# 2312_ESP32.net
KiCad netlist of a schematic drawn in Altium Designer
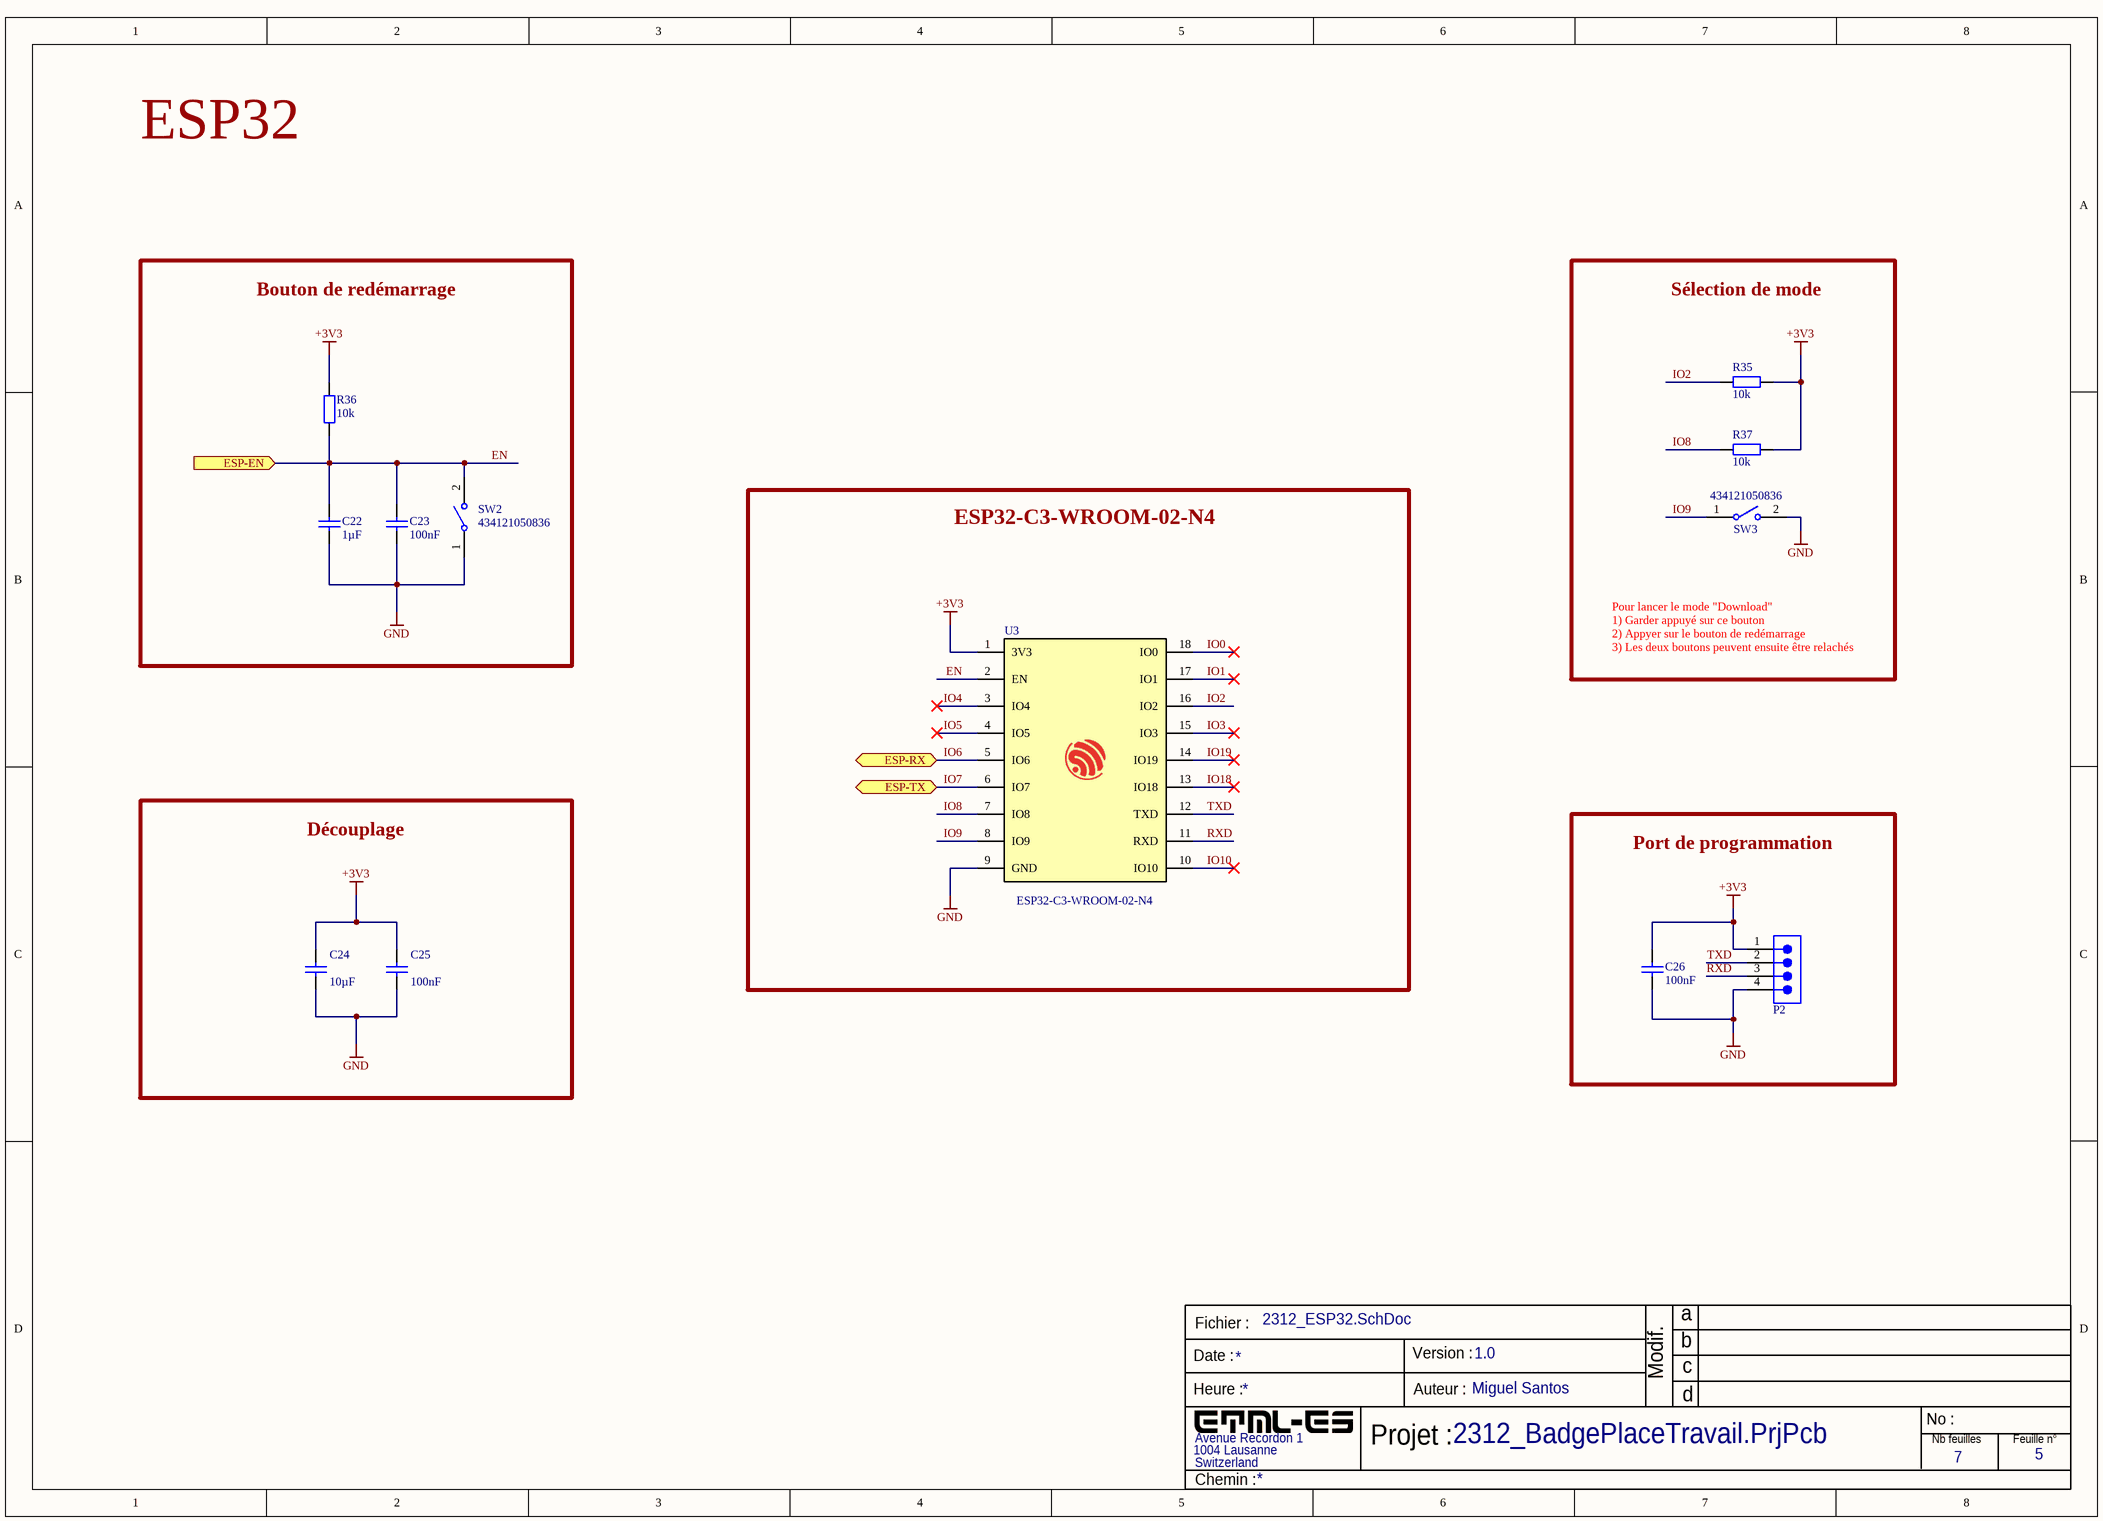
[diagram p0: 2312_ESP32.SchDoc]

(export (version "E")
  (design (tool "Eeschema 10.0.6"))
  (components
    (comp (ref "C22")
      (value "885012207022")
      (footprint "WCAP-CSGP_0805_L2W1.25H1.25")
      (description "WCAP-CSGP Multilayer Ceramic Chip Capacitor, General Purpose, size 0805, X7R, 1µF, 10VDC")
      (fields (field (name "MANUFACTURER") "Wurth Elektronik") (field (name "CAPACITANCE") "1µF"))
      (libsource (lib "WCAP-CSGP") (part "885012207022"))
    )
    (comp (ref "C23")
      (value "885012207016")
      (footprint "WCAP-CSGP_0805_L2W1.25H0.8_Reflow")
      (description "WCAP-CSGP Multilayer Ceramic Chip Capacitor, General Purpose, size 0805, X7R, 100nF, 10VDC")
      (fields (field (name "MANUFACTURER") "Wurth Elektronik") (field (name "CAPACITANCE") "100nF"))
      (libsource (lib "WCAP-CSGP") (part "885012207016"))
    )
    (comp (ref "C24")
      (value "885012107004")
      (footprint "WCAP-CSGP_0805_L2W1.25H1.25")
      (description "WCAP-CSGP Multilayer Ceramic Chip Capacitor, General Purpose, size 0805, X5R, 10µF, 6.3VDC")
      (fields (field (name "MANUFACTURER") "Wurth Elektronik") (field (name "CAPACITANCE") "10µF"))
      (libsource (lib "WCAP-CSGP") (part "885012107004"))
    )
    (comp (ref "C25")
      (value "885012207016")
      (footprint "WCAP-CSGP_0805_L2W1.25H0.8_Reflow")
      (description "WCAP-CSGP Multilayer Ceramic Chip Capacitor, General Purpose, size 0805, X7R, 100nF, 10VDC")
      (fields (field (name "MANUFACTURER") "Wurth Elektronik") (field (name "CAPACITANCE") "100nF"))
      (libsource (lib "WCAP-CSGP") (part "885012207016"))
    )
    (comp (ref "C26")
      (value "885012207016")
      (footprint "WCAP-CSGP_0805_L2W1.25H0.8_Reflow")
      (description "WCAP-CSGP Multilayer Ceramic Chip Capacitor, General Purpose, size 0805, X7R, 100nF, 10VDC")
      (fields (field (name "MANUFACTURER") "Wurth Elektronik") (field (name "CAPACITANCE") "100nF"))
      (libsource (lib "WCAP-CSGP") (part "885012207016"))
    )
    (comp (ref "P2")
      (value "61300411121")
      (footprint "61300411121")
      (description "WR-PHD Pin Header, THT, Vertical, pitch 2.54mm, 1 Row, 4P")
      (fields (field (name "MANUFACTURER") "Wurth Elektronik"))
      (libsource (lib "WR-PHD") (part "61300411121"))
    )
    (comp (ref "R35")
      (value "RES-0805")
      (footprint "2312-RES-0805")
      (description "SMD Resistor 0805, 10kΩ")
      (fields (field (name "RESISTANCE") "10k"))
      (libsource (lib "2312-MS-0805") (part "RES-0805"))
    )
    (comp (ref "R36")
      (value "RES-0805")
      (footprint "2312-RES-0805")
      (description "SMD Resistor 0805, 10kΩ")
      (fields (field (name "RESISTANCE") "10k"))
      (libsource (lib "2312-MS-0805") (part "RES-0805"))
    )
    (comp (ref "R37")
      (value "RES-0805")
      (footprint "2312-RES-0805")
      (description "SMD Resistor 0805, 10kΩ")
      (fields (field (name "RESISTANCE") "10k"))
      (libsource (lib "2312-MS-0805") (part "RES-0805"))
    )
    (comp (ref "SW2")
      (value "434121050836")
      (footprint "WS-TASV_L6W3.5H5_4341x10508x6")
      (description "WS-TASV SMT Tact Switch, L6 x W3.5 x H5mm, 360g, SPST-NO, 12V, 50mA")
      (fields (field (name "MANUFACTURER") "Wurth Elektronik"))
      (libsource (lib "WS-TASV") (part "434121050836"))
    )
    (comp (ref "SW3")
      (value "434121050836")
      (footprint "WS-TASV_L6W3.5H5_4341x10508x6")
      (description "WS-TASV SMT Tact Switch, L6 x W3.5 x H5mm, 360g, SPST-NO, 12V, 50mA")
      (fields (field (name "MANUFACTURER") "Wurth Elektronik"))
      (libsource (lib "WS-TASV") (part "434121050836"))
    )
    (comp (ref "U3")
      (value "ESP32-C3-WROOM-02-N4")
      (footprint "ESP32C3WROOM02N4")
      (fields (field (name "MOUSER PART NUMBER") "356-ESP32C3WROOM02N4"))
      (libsource (lib "ESP32-C3-WROOM-02-N4") (part "ESP32-C3-WROOM-02-N4"))
    )
  )
  (nets
    (net (code "1") (name "+3V3") (class "Default")
      (node (ref "C24") (pin "2") (pinfunction "2_2") (pintype "passive"))
      (node (ref "C25") (pin "2") (pinfunction "2_2") (pintype "passive"))
      (node (ref "C26") (pin "2") (pinfunction "2_2") (pintype "passive"))
      (node (ref "P2") (pin "1") (pinfunction "1_1") (pintype "passive"))
      (node (ref "R35") (pin "1") (pinfunction "1_1") (pintype "passive"))
      (node (ref "R36") (pin "1") (pinfunction "1_1") (pintype "passive"))
      (node (ref "R37") (pin "2") (pinfunction "2_2") (pintype "passive"))
      (node (ref "U3") (pin "1") (pinfunction "3V3_1") (pintype "passive"))
    )
    (net (code "2") (name "/EN") (class "Default")
      (node (ref "C22") (pin "2") (pinfunction "2_2") (pintype "passive"))
      (node (ref "C23") (pin "1") (pinfunction "1_1") (pintype "passive"))
      (node (ref "R36") (pin "2") (pinfunction "2_2") (pintype "passive"))
      (node (ref "SW2") (pin "2") (pinfunction "2_2") (pintype "passive"))
      (node (ref "U3") (pin "2") (pinfunction "EN_2") (pintype "passive"))
    )
    (net (code "3") (name "/IO0") (class "Default")
      (node (ref "U3") (pin "18") (pinfunction "IO0_18") (pintype "passive+no_connect"))
    )
    (net (code "4") (name "/IO1") (class "Default")
      (node (ref "U3") (pin "17") (pinfunction "IO1_17") (pintype "passive+no_connect"))
    )
    (net (code "5") (name "/IO2") (class "Default")
      (node (ref "R35") (pin "2") (pinfunction "2_2") (pintype "passive"))
      (node (ref "U3") (pin "16") (pinfunction "IO2_16") (pintype "passive"))
    )
    (net (code "6") (name "/IO3") (class "Default")
      (node (ref "U3") (pin "15") (pinfunction "IO3_15") (pintype "passive+no_connect"))
    )
    (net (code "7") (name "/IO4") (class "Default")
      (node (ref "U3") (pin "3") (pinfunction "IO4_3") (pintype "passive+no_connect"))
    )
    (net (code "8") (name "/IO5") (class "Default")
      (node (ref "U3") (pin "4") (pinfunction "IO5_4") (pintype "passive+no_connect"))
    )
    (net (code "9") (name "/IO6") (class "Default")
      (node (ref "U3") (pin "5") (pinfunction "IO6_5") (pintype "passive"))
    )
    (net (code "10") (name "/IO7") (class "Default")
      (node (ref "U3") (pin "6") (pinfunction "IO7_6") (pintype "passive"))
    )
    (net (code "11") (name "/IO8") (class "Default")
      (node (ref "R37") (pin "1") (pinfunction "1_1") (pintype "passive"))
      (node (ref "U3") (pin "7") (pinfunction "IO8_7") (pintype "passive"))
    )
    (net (code "12") (name "/IO9") (class "Default")
      (node (ref "SW3") (pin "1") (pinfunction "1_1") (pintype "passive"))
      (node (ref "U3") (pin "8") (pinfunction "IO9_8") (pintype "passive"))
    )
    (net (code "13") (name "/IO10") (class "Default")
      (node (ref "U3") (pin "10") (pinfunction "IO10_10") (pintype "passive+no_connect"))
    )
    (net (code "14") (name "/IO18") (class "Default")
      (node (ref "U3") (pin "13") (pinfunction "IO18_13") (pintype "passive+no_connect"))
    )
    (net (code "15") (name "/IO19") (class "Default")
      (node (ref "U3") (pin "14") (pinfunction "IO19_14") (pintype "passive+no_connect"))
    )
    (net (code "16") (name "/RXD") (class "Default")
      (node (ref "P2") (pin "3") (pinfunction "3_3") (pintype "passive"))
      (node (ref "U3") (pin "11") (pinfunction "RXD_11") (pintype "passive"))
    )
    (net (code "17") (name "/TXD") (class "Default")
      (node (ref "P2") (pin "2") (pinfunction "2_2") (pintype "passive"))
      (node (ref "U3") (pin "12") (pinfunction "TXD_12") (pintype "passive"))
    )
    (net (code "18") (name "GND") (class "Default")
      (node (ref "C22") (pin "1") (pinfunction "1_1") (pintype "passive"))
      (node (ref "C23") (pin "2") (pinfunction "2_2") (pintype "passive"))
      (node (ref "C24") (pin "1") (pinfunction "1_1") (pintype "passive"))
      (node (ref "C25") (pin "1") (pinfunction "1_1") (pintype "passive"))
      (node (ref "C26") (pin "1") (pinfunction "1_1") (pintype "passive"))
      (node (ref "P2") (pin "4") (pinfunction "4_4") (pintype "passive"))
      (node (ref "SW2") (pin "1") (pinfunction "1_1") (pintype "passive"))
      (node (ref "SW3") (pin "2") (pinfunction "2_2") (pintype "passive"))
      (node (ref "U3") (pin "9") (pinfunction "GND_9") (pintype "passive"))
    )
  )
)
